# NZP_Breakout.net
KiCad netlist of a schematic drawn in EAGLE
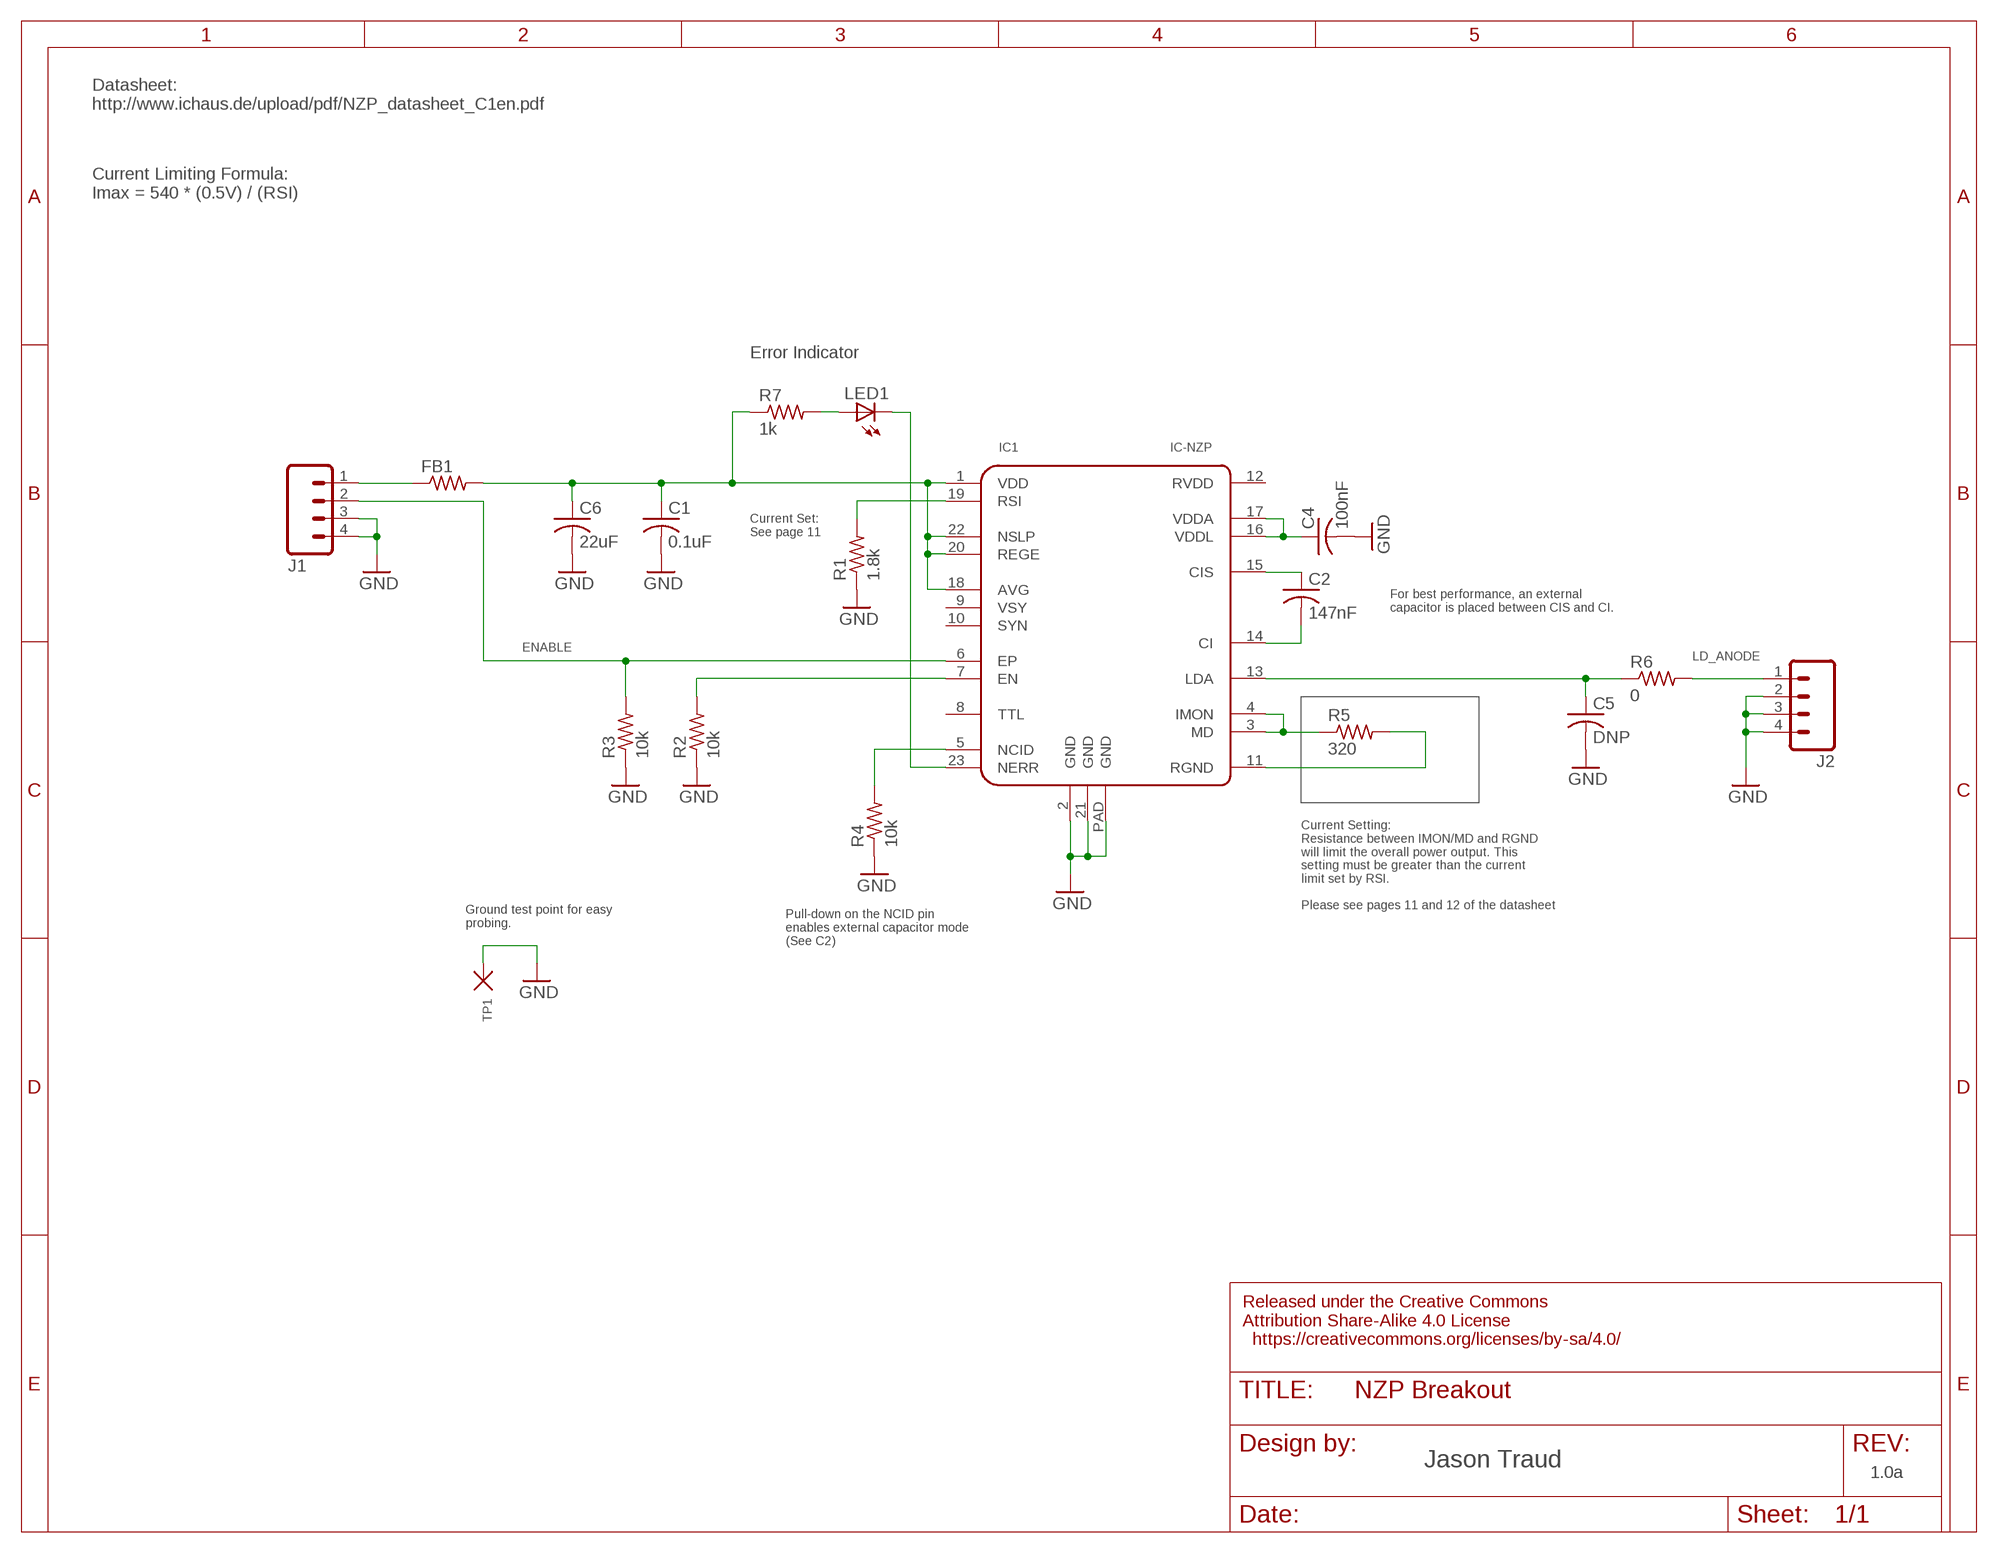
[diagram p0: schematic, sheet 1]

(export (version "E")
  (design (tool "Eeschema 10.0.6"))
  (components
    (comp (ref "C1")
      (value "0.1uF")
      (footprint "eagle-import:C0402")
      (libsource (lib "eagle-import") (part "C-USC0402"))
    )
    (comp (ref "C2")
      (value "147nF")
      (footprint "eagle-import:C0402")
      (libsource (lib "eagle-import") (part "C-USC0402"))
    )
    (comp (ref "C4")
      (value "100nF")
      (footprint "eagle-import:C0402")
      (libsource (lib "eagle-import") (part "C-USC0402"))
    )
    (comp (ref "C5")
      (value "DNP")
      (footprint "eagle-import:C0805")
      (libsource (lib "eagle-import") (part "C-USC0805"))
    )
    (comp (ref "C6")
      (value "22uF")
      (footprint "eagle-import:C1206")
      (libsource (lib "eagle-import") (part "C-USC1206"))
    )
    (comp (ref "FB1")
      (value "R-US_R0805")
      (footprint "eagle-import:R0805")
      (libsource (lib "eagle-import") (part "R-US_R0805"))
    )
    (comp (ref "IC1")
      (value "IC-NZP")
      (footprint "eagle-import:QFN24_PAD")
      (libsource (lib "eagle-import") (part "IC-NZP"))
    )
    (comp (ref "J1")
      (value "2X2")
      (footprint "eagle-import:2X2_1.27MM")
      (libsource (lib "eagle-import") (part "2X2"))
    )
    (comp (ref "J2")
      (value "2X2")
      (footprint "eagle-import:2X2_1.27MM")
      (libsource (lib "eagle-import") (part "2X2"))
    )
    (comp (ref "LED1")
      (value "LEDSML0805")
      (footprint "eagle-import:SML0805")
      (libsource (lib "eagle-import") (part "LEDSML0805"))
    )
    (comp (ref "R1")
      (value "1.8k")
      (footprint "eagle-import:R0402")
      (libsource (lib "eagle-import") (part "R-US_R0402"))
    )
    (comp (ref "R2")
      (value "10k")
      (footprint "eagle-import:R0402")
      (libsource (lib "eagle-import") (part "R-US_R0402"))
    )
    (comp (ref "R3")
      (value "10k")
      (footprint "eagle-import:R0402")
      (libsource (lib "eagle-import") (part "R-US_R0402"))
    )
    (comp (ref "R4")
      (value "10k")
      (footprint "eagle-import:R0402")
      (libsource (lib "eagle-import") (part "R-US_R0402"))
    )
    (comp (ref "R5")
      (value "320")
      (footprint "eagle-import:R0402")
      (libsource (lib "eagle-import") (part "R-US_R0402"))
    )
    (comp (ref "R6")
      (value "0")
      (footprint "eagle-import:R0805")
      (libsource (lib "eagle-import") (part "R-US_R0805"))
    )
    (comp (ref "R7")
      (value "1k")
      (footprint "eagle-import:R0402")
      (libsource (lib "eagle-import") (part "R-US_R0402"))
    )
    (comp (ref "TP1") (value "TP") (footprint "eagle-import:TP") (libsource (lib "eagle-import") (part "TP")))
  )
  (nets
    (net (code "1") (name "/ENABLE") (class "Default")
      (node (ref "IC1") (pin "6") (pinfunction "EP_6") (pintype "bidirectional"))
      (node (ref "J1") (pin "2") (pinfunction "2_2") (pintype "passive"))
      (node (ref "R3") (pin "2") (pinfunction "2_2") (pintype "passive"))
    )
    (net (code "2") (name "/LD_ANODE") (class "Default")
      (node (ref "J2") (pin "1") (pinfunction "1_1") (pintype "passive"))
      (node (ref "R6") (pin "2") (pinfunction "2_2") (pintype "passive"))
    )
    (net (code "3") (name "GND") (class "Default")
      (node (ref "C1") (pin "2") (pinfunction "2_2") (pintype "passive"))
      (node (ref "C4") (pin "2") (pinfunction "2_2") (pintype "passive"))
      (node (ref "C5") (pin "2") (pinfunction "2_2") (pintype "passive"))
      (node (ref "C6") (pin "2") (pinfunction "2_2") (pintype "passive"))
      (node (ref "IC1") (pin "2") (pinfunction "GND_2") (pintype "bidirectional"))
      (node (ref "IC1") (pin "21") (pinfunction "GND_21") (pintype "bidirectional"))
      (node (ref "IC1") (pin "PAD") (pinfunction "GND_PAD") (pintype "bidirectional"))
      (node (ref "J1") (pin "3") (pinfunction "3_3") (pintype "passive"))
      (node (ref "J1") (pin "4") (pinfunction "4_4") (pintype "passive"))
      (node (ref "J2") (pin "2") (pinfunction "2_2") (pintype "passive"))
      (node (ref "J2") (pin "3") (pinfunction "3_3") (pintype "passive"))
      (node (ref "J2") (pin "4") (pinfunction "4_4") (pintype "passive"))
      (node (ref "R1") (pin "1") (pinfunction "1_1") (pintype "passive"))
      (node (ref "R2") (pin "1") (pinfunction "1_1") (pintype "passive"))
      (node (ref "R3") (pin "1") (pinfunction "1_1") (pintype "passive"))
      (node (ref "R4") (pin "1") (pinfunction "1_1") (pintype "passive"))
      (node (ref "TP1") (pin "P$1") (pinfunction "P$1_P$1") (pintype "bidirectional"))
    )
    (net (code "4") (name "Net-(FB1-Pad1)") (class "Default")
      (node (ref "FB1") (pin "1") (pinfunction "1_1") (pintype "passive"))
      (node (ref "J1") (pin "1") (pinfunction "1_1") (pintype "passive"))
    )
    (net (code "5") (name "Net-(IC1-AVG)") (class "Default")
      (node (ref "C1") (pin "1") (pinfunction "1_1") (pintype "passive"))
      (node (ref "C6") (pin "1") (pinfunction "1_1") (pintype "passive"))
      (node (ref "FB1") (pin "2") (pinfunction "2_2") (pintype "passive"))
      (node (ref "IC1") (pin "1") (pinfunction "VDD_1") (pintype "bidirectional"))
      (node (ref "IC1") (pin "18") (pinfunction "AVG_18") (pintype "bidirectional"))
      (node (ref "IC1") (pin "20") (pinfunction "REGE_20") (pintype "bidirectional"))
      (node (ref "IC1") (pin "22") (pinfunction "NSLP_22") (pintype "bidirectional"))
      (node (ref "R7") (pin "1") (pinfunction "1_1") (pintype "passive"))
    )
    (net (code "6") (name "Net-(IC1-CI)") (class "Default")
      (node (ref "C2") (pin "2") (pinfunction "2_2") (pintype "passive"))
      (node (ref "IC1") (pin "14") (pinfunction "CI_14") (pintype "bidirectional"))
    )
    (net (code "7") (name "Net-(IC1-CIS)") (class "Default")
      (node (ref "C2") (pin "1") (pinfunction "1_1") (pintype "passive"))
      (node (ref "IC1") (pin "15") (pinfunction "CIS_15") (pintype "bidirectional"))
    )
    (net (code "8") (name "Net-(IC1-EN)") (class "Default")
      (node (ref "IC1") (pin "7") (pinfunction "EN_7") (pintype "bidirectional"))
      (node (ref "R2") (pin "2") (pinfunction "2_2") (pintype "passive"))
    )
    (net (code "9") (name "Net-(IC1-IMON)") (class "Default")
      (node (ref "IC1") (pin "3") (pinfunction "MD_3") (pintype "bidirectional"))
      (node (ref "IC1") (pin "4") (pinfunction "IMON_4") (pintype "bidirectional"))
      (node (ref "R5") (pin "1") (pinfunction "1_1") (pintype "passive"))
    )
    (net (code "10") (name "Net-(IC1-LDA)") (class "Default")
      (node (ref "C5") (pin "1") (pinfunction "1_1") (pintype "passive"))
      (node (ref "IC1") (pin "13") (pinfunction "LDA_13") (pintype "bidirectional"))
      (node (ref "R6") (pin "1") (pinfunction "1_1") (pintype "passive"))
    )
    (net (code "11") (name "Net-(IC1-NCID)") (class "Default")
      (node (ref "IC1") (pin "5") (pinfunction "NCID_5") (pintype "bidirectional"))
      (node (ref "R4") (pin "2") (pinfunction "2_2") (pintype "passive"))
    )
    (net (code "12") (name "Net-(IC1-NERR)") (class "Default")
      (node (ref "IC1") (pin "23") (pinfunction "NERR_23") (pintype "bidirectional"))
      (node (ref "LED1") (pin "C") (pinfunction "C_C") (pintype "passive"))
    )
    (net (code "13") (name "Net-(IC1-RGND)") (class "Default")
      (node (ref "IC1") (pin "11") (pinfunction "RGND_11") (pintype "bidirectional"))
      (node (ref "R5") (pin "2") (pinfunction "2_2") (pintype "passive"))
    )
    (net (code "14") (name "Net-(IC1-RSI)") (class "Default")
      (node (ref "IC1") (pin "19") (pinfunction "RSI_19") (pintype "bidirectional"))
      (node (ref "R1") (pin "2") (pinfunction "2_2") (pintype "passive"))
    )
    (net (code "15") (name "Net-(IC1-VDDA)") (class "Default")
      (node (ref "C4") (pin "1") (pinfunction "1_1") (pintype "passive"))
      (node (ref "IC1") (pin "16") (pinfunction "VDDL_16") (pintype "bidirectional"))
      (node (ref "IC1") (pin "17") (pinfunction "VDDA_17") (pintype "bidirectional"))
    )
    (net (code "16") (name "Net-(LED1-PadA)") (class "Default")
      (node (ref "LED1") (pin "A") (pinfunction "A_A") (pintype "passive"))
      (node (ref "R7") (pin "2") (pinfunction "2_2") (pintype "passive"))
    )
    (net (code "17") (name "unconnected-(IC1-RVDD-Pad12)") (class "Default")
      (node (ref "IC1") (pin "12") (pinfunction "RVDD_12") (pintype "bidirectional"))
    )
    (net (code "18") (name "unconnected-(IC1-SYN-Pad10)") (class "Default")
      (node (ref "IC1") (pin "10") (pinfunction "SYN_10") (pintype "bidirectional"))
    )
    (net (code "19") (name "unconnected-(IC1-TTL-Pad8)") (class "Default")
      (node (ref "IC1") (pin "8") (pinfunction "TTL_8") (pintype "bidirectional"))
    )
    (net (code "20") (name "unconnected-(IC1-VSY-Pad9)") (class "Default")
      (node (ref "IC1") (pin "9") (pinfunction "VSY_9") (pintype "bidirectional"))
    )
  )
)
